# QFN68_DIP72_SMT_Schematic.net
KiCad netlist of a schematic drawn in Altium Designer
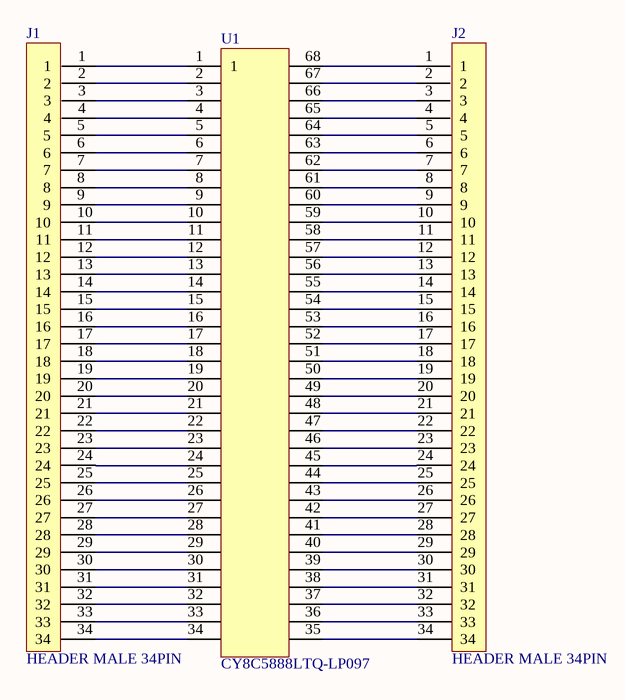
[diagram p0: QFN68_DIP72_SMT_Schematic.SchDoc]

(export (version "E")
  (design (tool "Eeschema 10.0.6"))
  (components
    (comp (ref "J1")
      (value "HEADER MALE 34PIN")
      (footprint "HDR_MALE_1x4_2.54mm")
      (description "Headers & Wire Housings 34P STR SR TMT HDR .76 AU .425IN LENGTH")
      (fields
        (field (name "MANUFACTURER") "Amphenol ICC / FCI")
        (field (name "MANUFACTURER PART NUMBER") "77311-101-34LF")
      )
      (libsource (lib "QFN68_DIP72_SMT_Schlib") (part "77311-101-34LF"))
    )
    (comp (ref "J2")
      (value "HEADER MALE 34PIN")
      (footprint "HDR_MALE_1x4_2.54mm")
      (description "Headers & Wire Housings 34P STR SR TMT HDR .76 AU .425IN LENGTH")
      (fields
        (field (name "MANUFACTURER") "Amphenol ICC / FCI")
        (field (name "MANUFACTURER PART NUMBER") "77311-101-34LF")
      )
      (libsource (lib "") (part "77311-101-34LF_1"))
    )
    (comp (ref "U1")
      (value "CY8C5888LTQ-LP097")
      (footprint "CYP-LTX68_L")
      (description "MCU 32-bit ARM Cortex M3 RISC 256KB Flash 1.8V/3.3V/5V 68-Pin QFN EP Tray")
      (fields (field (name "MANUFACTURER") "Cypress"))
      (libsource (lib "QFN68_DIP72_SMT_Schlib") (part "CY8C5888LTQ-LP097"))
    )
  )
  (nets
    (net (code "1") (name "Net-(J1-Pad1)") (class "Default")
      (node (ref "J1") (pin "1") (pinfunction "1_1") (pintype "passive"))
      (node (ref "U1") (pin "1") (pinfunction "1_1") (pintype "passive"))
    )
    (net (code "2") (name "Net-(J1-Pad2)") (class "Default")
      (node (ref "J1") (pin "2") (pinfunction "2_2") (pintype "passive"))
      (node (ref "U1") (pin "2") (pintype "passive"))
    )
    (net (code "3") (name "Net-(J1-Pad3)") (class "Default")
      (node (ref "J1") (pin "3") (pinfunction "3_3") (pintype "passive"))
      (node (ref "U1") (pin "3") (pintype "passive"))
    )
    (net (code "4") (name "Net-(J1-Pad4)") (class "Default")
      (node (ref "J1") (pin "4") (pinfunction "4_4") (pintype "passive"))
      (node (ref "U1") (pin "4") (pintype "passive"))
    )
    (net (code "5") (name "Net-(J1-Pad5)") (class "Default")
      (node (ref "J1") (pin "5") (pinfunction "5_5") (pintype "passive"))
      (node (ref "U1") (pin "5") (pintype "passive"))
    )
    (net (code "6") (name "Net-(J1-Pad6)") (class "Default")
      (node (ref "J1") (pin "6") (pinfunction "6_6") (pintype "passive"))
      (node (ref "U1") (pin "6") (pintype "passive"))
    )
    (net (code "7") (name "Net-(J1-Pad7)") (class "Default")
      (node (ref "J1") (pin "7") (pinfunction "7_7") (pintype "passive"))
      (node (ref "U1") (pin "7") (pintype "passive"))
    )
    (net (code "8") (name "Net-(J1-Pad8)") (class "Default")
      (node (ref "J1") (pin "8") (pinfunction "8_8") (pintype "passive"))
      (node (ref "U1") (pin "8") (pintype "passive"))
    )
    (net (code "9") (name "Net-(J1-Pad9)") (class "Default")
      (node (ref "J1") (pin "9") (pinfunction "9_9") (pintype "passive"))
      (node (ref "U1") (pin "9") (pintype "passive"))
    )
    (net (code "10") (name "Net-(J1-Pad10)") (class "Default")
      (node (ref "J1") (pin "10") (pinfunction "10_10") (pintype "passive"))
      (node (ref "U1") (pin "10") (pintype "passive"))
    )
    (net (code "11") (name "Net-(J1-Pad11)") (class "Default")
      (node (ref "J1") (pin "11") (pinfunction "11_11") (pintype "passive"))
      (node (ref "U1") (pin "11") (pintype "passive"))
    )
    (net (code "12") (name "Net-(J1-Pad12)") (class "Default")
      (node (ref "J1") (pin "12") (pinfunction "12_12") (pintype "passive"))
      (node (ref "U1") (pin "12") (pintype "passive"))
    )
    (net (code "13") (name "Net-(J1-Pad13)") (class "Default")
      (node (ref "J1") (pin "13") (pinfunction "13_13") (pintype "passive"))
      (node (ref "U1") (pin "13") (pintype "passive"))
    )
    (net (code "14") (name "Net-(J1-Pad14)") (class "Default")
      (node (ref "J1") (pin "14") (pinfunction "14_14") (pintype "passive"))
      (node (ref "U1") (pin "14") (pintype "passive"))
    )
    (net (code "15") (name "Net-(J1-Pad15)") (class "Default")
      (node (ref "J1") (pin "15") (pinfunction "15_15") (pintype "passive"))
      (node (ref "U1") (pin "15") (pintype "passive"))
    )
    (net (code "16") (name "Net-(J1-Pad16)") (class "Default")
      (node (ref "J1") (pin "16") (pinfunction "16_16") (pintype "passive"))
      (node (ref "U1") (pin "16") (pintype "passive"))
    )
    (net (code "17") (name "Net-(J1-Pad17)") (class "Default")
      (node (ref "J1") (pin "17") (pinfunction "17_17") (pintype "passive"))
      (node (ref "U1") (pin "17") (pintype "passive"))
    )
    (net (code "18") (name "Net-(J1-Pad18)") (class "Default")
      (node (ref "J1") (pin "18") (pinfunction "18_18") (pintype "passive"))
      (node (ref "U1") (pin "18") (pintype "passive"))
    )
    (net (code "19") (name "Net-(J1-Pad19)") (class "Default")
      (node (ref "J1") (pin "19") (pinfunction "19_19") (pintype "passive"))
      (node (ref "U1") (pin "19") (pintype "passive"))
    )
    (net (code "20") (name "Net-(J1-Pad20)") (class "Default")
      (node (ref "J1") (pin "20") (pinfunction "20_20") (pintype "passive"))
      (node (ref "U1") (pin "20") (pintype "passive"))
    )
    (net (code "21") (name "Net-(J1-Pad21)") (class "Default")
      (node (ref "J1") (pin "21") (pinfunction "21_21") (pintype "passive"))
      (node (ref "U1") (pin "21") (pintype "passive"))
    )
    (net (code "22") (name "Net-(J1-Pad22)") (class "Default")
      (node (ref "J1") (pin "22") (pinfunction "22_22") (pintype "passive"))
      (node (ref "U1") (pin "22") (pintype "passive"))
    )
    (net (code "23") (name "Net-(J1-Pad23)") (class "Default")
      (node (ref "J1") (pin "23") (pinfunction "23_23") (pintype "passive"))
      (node (ref "U1") (pin "23") (pintype "passive"))
    )
    (net (code "24") (name "Net-(J1-Pad24)") (class "Default")
      (node (ref "J1") (pin "24") (pinfunction "24_24") (pintype "passive"))
      (node (ref "U1") (pin "24") (pintype "passive"))
    )
    (net (code "25") (name "Net-(J1-Pad25)") (class "Default")
      (node (ref "J1") (pin "25") (pinfunction "25_25") (pintype "passive"))
      (node (ref "U1") (pin "25") (pintype "passive"))
    )
    (net (code "26") (name "Net-(J1-Pad26)") (class "Default")
      (node (ref "J1") (pin "26") (pinfunction "26_26") (pintype "passive"))
      (node (ref "U1") (pin "26") (pintype "passive"))
    )
    (net (code "27") (name "Net-(J1-Pad27)") (class "Default")
      (node (ref "J1") (pin "27") (pinfunction "27_27") (pintype "passive"))
      (node (ref "U1") (pin "27") (pintype "passive"))
    )
    (net (code "28") (name "Net-(J1-Pad28)") (class "Default")
      (node (ref "J1") (pin "28") (pinfunction "28_28") (pintype "passive"))
      (node (ref "U1") (pin "28") (pintype "passive"))
    )
    (net (code "29") (name "Net-(J1-Pad29)") (class "Default")
      (node (ref "J1") (pin "29") (pinfunction "29_29") (pintype "passive"))
      (node (ref "U1") (pin "29") (pintype "passive"))
    )
    (net (code "30") (name "Net-(J1-Pad30)") (class "Default")
      (node (ref "J1") (pin "30") (pinfunction "30_30") (pintype "passive"))
      (node (ref "U1") (pin "30") (pintype "passive"))
    )
    (net (code "31") (name "Net-(J1-Pad31)") (class "Default")
      (node (ref "J1") (pin "31") (pinfunction "31_31") (pintype "passive"))
      (node (ref "U1") (pin "31") (pintype "passive"))
    )
    (net (code "32") (name "Net-(J1-Pad32)") (class "Default")
      (node (ref "J1") (pin "32") (pinfunction "32_32") (pintype "passive"))
      (node (ref "U1") (pin "32") (pintype "passive"))
    )
    (net (code "33") (name "Net-(J1-Pad33)") (class "Default")
      (node (ref "J1") (pin "33") (pinfunction "33_33") (pintype "passive"))
      (node (ref "U1") (pin "33") (pintype "passive"))
    )
    (net (code "34") (name "Net-(J1-Pad34)") (class "Default")
      (node (ref "J1") (pin "34") (pinfunction "34_34") (pintype "passive"))
      (node (ref "U1") (pin "34") (pintype "passive"))
    )
    (net (code "35") (name "Net-(J2-Pad1)") (class "Default")
      (node (ref "J2") (pin "1") (pinfunction "1_1") (pintype "passive"))
      (node (ref "U1") (pin "68") (pintype "passive"))
    )
    (net (code "36") (name "Net-(J2-Pad2)") (class "Default")
      (node (ref "J2") (pin "2") (pinfunction "2_2") (pintype "passive"))
      (node (ref "U1") (pin "67") (pintype "passive"))
    )
    (net (code "37") (name "Net-(J2-Pad3)") (class "Default")
      (node (ref "J2") (pin "3") (pinfunction "3_3") (pintype "passive"))
      (node (ref "U1") (pin "66") (pintype "passive"))
    )
    (net (code "38") (name "Net-(J2-Pad4)") (class "Default")
      (node (ref "J2") (pin "4") (pinfunction "4_4") (pintype "passive"))
      (node (ref "U1") (pin "65") (pintype "passive"))
    )
    (net (code "39") (name "Net-(J2-Pad5)") (class "Default")
      (node (ref "J2") (pin "5") (pinfunction "5_5") (pintype "passive"))
      (node (ref "U1") (pin "64") (pintype "passive"))
    )
    (net (code "40") (name "Net-(J2-Pad6)") (class "Default")
      (node (ref "J2") (pin "6") (pinfunction "6_6") (pintype "passive"))
      (node (ref "U1") (pin "63") (pintype "passive"))
    )
    (net (code "41") (name "Net-(J2-Pad7)") (class "Default")
      (node (ref "J2") (pin "7") (pinfunction "7_7") (pintype "passive"))
      (node (ref "U1") (pin "62") (pintype "passive"))
    )
    (net (code "42") (name "Net-(J2-Pad8)") (class "Default")
      (node (ref "J2") (pin "8") (pinfunction "8_8") (pintype "passive"))
      (node (ref "U1") (pin "61") (pintype "passive"))
    )
    (net (code "43") (name "Net-(J2-Pad9)") (class "Default")
      (node (ref "J2") (pin "9") (pinfunction "9_9") (pintype "passive"))
      (node (ref "U1") (pin "60") (pintype "passive"))
    )
    (net (code "44") (name "Net-(J2-Pad10)") (class "Default")
      (node (ref "J2") (pin "10") (pinfunction "10_10") (pintype "passive"))
      (node (ref "U1") (pin "59") (pintype "passive"))
    )
    (net (code "45") (name "Net-(J2-Pad11)") (class "Default")
      (node (ref "J2") (pin "11") (pinfunction "11_11") (pintype "passive"))
      (node (ref "U1") (pin "58") (pintype "passive"))
    )
    (net (code "46") (name "Net-(J2-Pad12)") (class "Default")
      (node (ref "J2") (pin "12") (pinfunction "12_12") (pintype "passive"))
      (node (ref "U1") (pin "57") (pintype "passive"))
    )
    (net (code "47") (name "Net-(J2-Pad13)") (class "Default")
      (node (ref "J2") (pin "13") (pinfunction "13_13") (pintype "passive"))
      (node (ref "U1") (pin "56") (pintype "passive"))
    )
    (net (code "48") (name "Net-(J2-Pad14)") (class "Default")
      (node (ref "J2") (pin "14") (pinfunction "14_14") (pintype "passive"))
      (node (ref "U1") (pin "55") (pintype "passive"))
    )
    (net (code "49") (name "Net-(J2-Pad15)") (class "Default")
      (node (ref "J2") (pin "15") (pinfunction "15_15") (pintype "passive"))
      (node (ref "U1") (pin "54") (pintype "passive"))
    )
    (net (code "50") (name "Net-(J2-Pad16)") (class "Default")
      (node (ref "J2") (pin "16") (pinfunction "16_16") (pintype "passive"))
      (node (ref "U1") (pin "53") (pintype "passive"))
    )
    (net (code "51") (name "Net-(J2-Pad17)") (class "Default")
      (node (ref "J2") (pin "17") (pinfunction "17_17") (pintype "passive"))
      (node (ref "U1") (pin "52") (pintype "passive"))
    )
    (net (code "52") (name "Net-(J2-Pad18)") (class "Default")
      (node (ref "J2") (pin "18") (pinfunction "18_18") (pintype "passive"))
      (node (ref "U1") (pin "51") (pintype "passive"))
    )
    (net (code "53") (name "Net-(J2-Pad19)") (class "Default")
      (node (ref "J2") (pin "19") (pinfunction "19_19") (pintype "passive"))
      (node (ref "U1") (pin "50") (pintype "passive"))
    )
    (net (code "54") (name "Net-(J2-Pad20)") (class "Default")
      (node (ref "J2") (pin "20") (pinfunction "20_20") (pintype "passive"))
      (node (ref "U1") (pin "49") (pintype "passive"))
    )
    (net (code "55") (name "Net-(J2-Pad21)") (class "Default")
      (node (ref "J2") (pin "21") (pinfunction "21_21") (pintype "passive"))
      (node (ref "U1") (pin "48") (pintype "passive"))
    )
    (net (code "56") (name "Net-(J2-Pad22)") (class "Default")
      (node (ref "J2") (pin "22") (pinfunction "22_22") (pintype "passive"))
      (node (ref "U1") (pin "47") (pintype "passive"))
    )
    (net (code "57") (name "Net-(J2-Pad23)") (class "Default")
      (node (ref "J2") (pin "23") (pinfunction "23_23") (pintype "passive"))
      (node (ref "U1") (pin "46") (pintype "passive"))
    )
    (net (code "58") (name "Net-(J2-Pad24)") (class "Default")
      (node (ref "J2") (pin "24") (pinfunction "24_24") (pintype "passive"))
      (node (ref "U1") (pin "45") (pintype "passive"))
    )
    (net (code "59") (name "Net-(J2-Pad25)") (class "Default")
      (node (ref "J2") (pin "25") (pinfunction "25_25") (pintype "passive"))
      (node (ref "U1") (pin "44") (pintype "passive"))
    )
    (net (code "60") (name "Net-(J2-Pad26)") (class "Default")
      (node (ref "J2") (pin "26") (pinfunction "26_26") (pintype "passive"))
      (node (ref "U1") (pin "43") (pintype "passive"))
    )
    (net (code "61") (name "Net-(J2-Pad27)") (class "Default")
      (node (ref "J2") (pin "27") (pinfunction "27_27") (pintype "passive"))
      (node (ref "U1") (pin "42") (pintype "passive"))
    )
    (net (code "62") (name "Net-(J2-Pad28)") (class "Default")
      (node (ref "J2") (pin "28") (pinfunction "28_28") (pintype "passive"))
      (node (ref "U1") (pin "41") (pintype "passive"))
    )
    (net (code "63") (name "Net-(J2-Pad29)") (class "Default")
      (node (ref "J2") (pin "29") (pinfunction "29_29") (pintype "passive"))
      (node (ref "U1") (pin "40") (pintype "passive"))
    )
    (net (code "64") (name "Net-(J2-Pad30)") (class "Default")
      (node (ref "J2") (pin "30") (pinfunction "30_30") (pintype "passive"))
      (node (ref "U1") (pin "39") (pintype "passive"))
    )
    (net (code "65") (name "Net-(J2-Pad31)") (class "Default")
      (node (ref "J2") (pin "31") (pinfunction "31_31") (pintype "passive"))
      (node (ref "U1") (pin "38") (pintype "passive"))
    )
    (net (code "66") (name "Net-(J2-Pad32)") (class "Default")
      (node (ref "J2") (pin "32") (pinfunction "32_32") (pintype "passive"))
      (node (ref "U1") (pin "37") (pintype "passive"))
    )
    (net (code "67") (name "Net-(J2-Pad33)") (class "Default")
      (node (ref "J2") (pin "33") (pinfunction "33_33") (pintype "passive"))
      (node (ref "U1") (pin "36") (pintype "passive"))
    )
    (net (code "68") (name "Net-(J2-Pad34)") (class "Default")
      (node (ref "J2") (pin "34") (pinfunction "34_34") (pintype "passive"))
      (node (ref "U1") (pin "35") (pintype "passive"))
    )
  )
)
